# DoubleLineInModuel.net
KiCad netlist of a schematic drawn in EAGLE
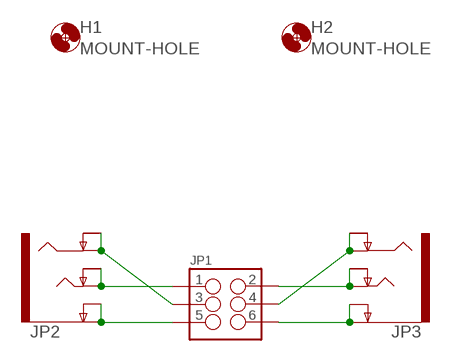
[diagram p0: schematic, sheet 1]

(export (version "E")
  (design (tool "Eeschema 10.0.6"))
  (components
    (comp (ref "H1")
      (value "MOUNT-HOLE")
      (footprint "eagle-import:3.2-NOMARKINGS-SMALLSAFEZONE")
      (libsource (lib "eagle-import") (part "MOUNT-HOLE"))
    )
    (comp (ref "H2")
      (value "MOUNT-HOLE")
      (footprint "eagle-import:3.2-NOMARKINGS-SMALLSAFEZONE")
      (libsource (lib "eagle-import") (part "MOUNT-HOLE"))
    )
    (comp (ref "JP1")
      (value "M03X2")
      (footprint "eagle-import:2X3-SHROUDED")
      (libsource (lib "eagle-import") (part "M03X2"))
    )
    (comp (ref "JP2")
      (value "AUDIO-JACK4-.25-HORIZ-TRS")
      (footprint "eagle-import:AUDIO-JACK-.25-INCH-HORIZ-PTH")
      (libsource (lib "eagle-import") (part "AUDIO-JACK4-.25-HORIZ-TRS"))
    )
    (comp (ref "JP3")
      (value "AUDIO-JACK4-.25-HORIZ-TRS")
      (footprint "eagle-import:AUDIO-JACK-.25-INCH-HORIZ-PTH")
      (libsource (lib "eagle-import") (part "AUDIO-JACK4-.25-HORIZ-TRS"))
    )
  )
  (nets
    (net (code "1") (name "Net-(JP2-EARTH)") (class "Default")
      (node (ref "JP1") (pin "5") (pinfunction "5_5") (pintype "bidirectional"))
      (node (ref "JP2") (pin "P$2") (pinfunction "EARTH_P$2") (pintype "bidirectional"))
      (node (ref "JP2") (pin "P$3") (pinfunction "EARTH-NORM_P$3") (pintype "bidirectional"))
    )
    (net (code "2") (name "Net-(JP2-RING)") (class "Default")
      (node (ref "JP1") (pin "3") (pinfunction "3_3") (pintype "bidirectional"))
      (node (ref "JP2") (pin "P$4") (pinfunction "RING_P$4") (pintype "bidirectional"))
      (node (ref "JP2") (pin "P$5") (pinfunction "RING-NORM_P$5") (pintype "bidirectional"))
    )
    (net (code "3") (name "Net-(JP2-TIP)") (class "Default")
      (node (ref "JP1") (pin "1") (pinfunction "1_1") (pintype "bidirectional"))
      (node (ref "JP2") (pin "P$6") (pinfunction "TIP_P$6") (pintype "bidirectional"))
      (node (ref "JP2") (pin "P$7") (pinfunction "TIP-NORM_P$7") (pintype "bidirectional"))
    )
    (net (code "4") (name "Net-(JP3-EARTH)") (class "Default")
      (node (ref "JP1") (pin "6") (pinfunction "6_6") (pintype "bidirectional"))
      (node (ref "JP3") (pin "P$2") (pinfunction "EARTH_P$2") (pintype "bidirectional"))
      (node (ref "JP3") (pin "P$3") (pinfunction "EARTH-NORM_P$3") (pintype "bidirectional"))
    )
    (net (code "5") (name "Net-(JP3-RING)") (class "Default")
      (node (ref "JP1") (pin "4") (pinfunction "4_4") (pintype "bidirectional"))
      (node (ref "JP3") (pin "P$4") (pinfunction "RING_P$4") (pintype "bidirectional"))
      (node (ref "JP3") (pin "P$5") (pinfunction "RING-NORM_P$5") (pintype "bidirectional"))
    )
    (net (code "6") (name "Net-(JP3-TIP)") (class "Default")
      (node (ref "JP1") (pin "2") (pinfunction "2_2") (pintype "bidirectional"))
      (node (ref "JP3") (pin "P$6") (pinfunction "TIP_P$6") (pintype "bidirectional"))
      (node (ref "JP3") (pin "P$7") (pinfunction "TIP-NORM_P$7") (pintype "bidirectional"))
    )
  )
)
